# ftcontrol.net
KiCad netlist of a schematic drawn in EAGLE
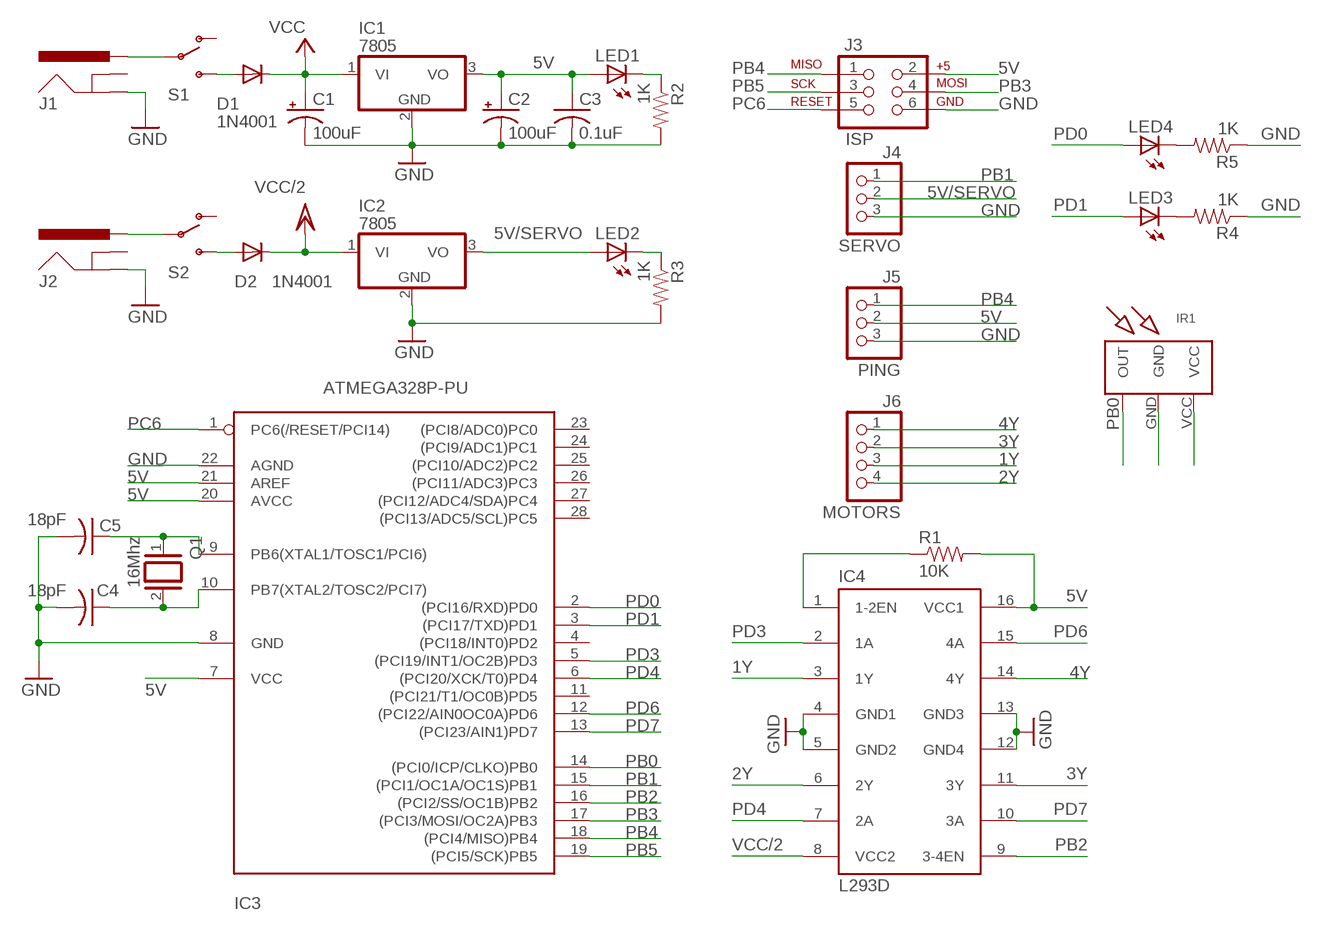
[diagram p0: schematic, sheet 1]

(export (version "E")
  (design (tool "Eeschema 10.0.6"))
  (components
    (comp (ref "C1")
      (value "100uF")
      (footprint "eagle-import:CPOL-RADIAL-100UF-25V")
      (libsource (lib "eagle-import") (part "CAP_POLPTH1"))
    )
    (comp (ref "C2")
      (value "100uF")
      (footprint "eagle-import:CPOL-RADIAL-10UF-25V")
      (libsource (lib "eagle-import") (part "CAP_POLPTH2"))
    )
    (comp (ref "C3")
      (value "0.1uF")
      (footprint "eagle-import:C025-025X050")
      (libsource (lib "eagle-import") (part "C-US025-025X050"))
    )
    (comp (ref "C4")
      (value "18pF")
      (footprint "eagle-import:C025-025X050")
      (libsource (lib "eagle-import") (part "C-US025-025X050"))
    )
    (comp (ref "C5")
      (value "18pF")
      (footprint "eagle-import:C025-025X050")
      (libsource (lib "eagle-import") (part "C-US025-025X050"))
    )
    (comp (ref "D1")
      (value "1N4001")
      (footprint "eagle-import:DIODE-1N4001")
      (libsource (lib "eagle-import") (part "DIODEPTH"))
    )
    (comp (ref "D2")
      (value "1N4001")
      (footprint "eagle-import:DIODE-1N4001")
      (libsource (lib "eagle-import") (part "DIODEPTH"))
    )
    (comp (ref "IC1")
      (value "7805")
      (footprint "eagle-import:TO220V")
      (libsource (lib "eagle-import") (part "78TV05"))
    )
    (comp (ref "IC2")
      (value "7805")
      (footprint "eagle-import:TO220V")
      (libsource (lib "eagle-import") (part "78TV05"))
    )
    (comp (ref "IC3")
      (value "ATMEGA328P-PU")
      (footprint "eagle-import:DIL28-3")
      (libsource (lib "eagle-import") (part "ATMEGA168P-20"))
    )
    (comp (ref "IC4")
      (value "L293D")
      (footprint "eagle-import:DIL16")
      (libsource (lib "eagle-import") (part "L293D"))
    )
    (comp (ref "IR1")
      (value "IR_TSOP4838")
      (footprint "eagle-import:TSOP_4838")
      (libsource (lib "eagle-import") (part "IR_TSOP4838"))
    )
    (comp (ref "J1")
      (value "POWER_JACKPTH")
      (footprint "eagle-import:POWER_JACK_PTH")
      (libsource (lib "eagle-import") (part "POWER_JACKPTH"))
    )
    (comp (ref "J2")
      (value "POWER_JACKPTH")
      (footprint "eagle-import:POWER_JACK_PTH")
      (libsource (lib "eagle-import") (part "POWER_JACKPTH"))
    )
    (comp (ref "J3")
      (value "ISP")
      (footprint "eagle-import:2X3")
      (libsource (lib "eagle-import") (part "AVR_SPI_PRG_6PTH"))
    )
    (comp (ref "J4")
      (value "SERVO")
      (footprint "eagle-import:1X03")
      (libsource (lib "eagle-import") (part "PINHD-1X3"))
    )
    (comp (ref "J5")
      (value "PING")
      (footprint "eagle-import:1X03")
      (libsource (lib "eagle-import") (part "PINHD-1X3"))
    )
    (comp (ref "J6")
      (value "MOTORS")
      (footprint "eagle-import:1X04")
      (libsource (lib "eagle-import") (part "PINHD-1X4"))
    )
    (comp (ref "LED1")
      (value "LED3MM")
      (footprint "eagle-import:LED3MM")
      (libsource (lib "eagle-import") (part "LED3MM"))
    )
    (comp (ref "LED2")
      (value "LED3MM")
      (footprint "eagle-import:LED3MM")
      (libsource (lib "eagle-import") (part "LED3MM"))
    )
    (comp (ref "LED3")
      (value "LED3MM")
      (footprint "eagle-import:LED3MM")
      (libsource (lib "eagle-import") (part "LED3MM"))
    )
    (comp (ref "LED4")
      (value "LED3MM")
      (footprint "eagle-import:LED3MM")
      (libsource (lib "eagle-import") (part "LED3MM"))
    )
    (comp (ref "Q1")
      (value "16Mhz")
      (footprint "eagle-import:QS")
      (libsource (lib "eagle-import") (part "XTAL/S"))
    )
    (comp (ref "R1")
      (value "10K")
      (footprint "eagle-import:AXIAL-0.4")
      (libsource (lib "eagle-import") (part "RESISTORPTH-1/4W"))
    )
    (comp (ref "R2")
      (value "1K")
      (footprint "eagle-import:AXIAL-0.4")
      (libsource (lib "eagle-import") (part "RESISTORPTH-1/4W"))
    )
    (comp (ref "R3")
      (value "1K")
      (footprint "eagle-import:AXIAL-0.4")
      (libsource (lib "eagle-import") (part "RESISTORPTH-1/4W"))
    )
    (comp (ref "R4")
      (value "1K")
      (footprint "eagle-import:AXIAL-0.4")
      (libsource (lib "eagle-import") (part "RESISTORPTH-1/4W"))
    )
    (comp (ref "R5")
      (value "1K")
      (footprint "eagle-import:AXIAL-0.4")
      (libsource (lib "eagle-import") (part "RESISTORPTH-1/4W"))
    )
    (comp (ref "S1")
      (value "SWITCH-SPDTPTH")
      (footprint "eagle-import:SWITCH-SPDT")
      (libsource (lib "eagle-import") (part "SWITCH-SPDTPTH"))
    )
    (comp (ref "S2")
      (value "SWITCH-SPDTPTH")
      (footprint "eagle-import:SWITCH-SPDT")
      (libsource (lib "eagle-import") (part "SWITCH-SPDTPTH"))
    )
  )
  (nets
    (net (code "1") (name "/1Y") (class "Default")
      (node (ref "IC4") (pin "3") (pinfunction "1Y_3") (pintype "output"))
      (node (ref "J6") (pin "3") (pinfunction "3_3") (pintype "passive"))
    )
    (net (code "2") (name "/2Y") (class "Default")
      (node (ref "IC4") (pin "6") (pinfunction "2Y_6") (pintype "output"))
      (node (ref "J6") (pin "4") (pinfunction "4_4") (pintype "passive"))
    )
    (net (code "3") (name "/3Y") (class "Default")
      (node (ref "IC4") (pin "11") (pinfunction "3Y_11") (pintype "output"))
      (node (ref "J6") (pin "2") (pinfunction "2_2") (pintype "passive"))
    )
    (net (code "4") (name "/4Y") (class "Default")
      (node (ref "IC4") (pin "14") (pinfunction "4Y_14") (pintype "output"))
      (node (ref "J6") (pin "1") (pinfunction "1_1") (pintype "passive"))
    )
    (net (code "5") (name "/5V") (class "Default")
      (node (ref "C2") (pin "1") (pinfunction "+_1") (pintype "passive"))
      (node (ref "C3") (pin "1") (pinfunction "1_1") (pintype "passive"))
      (node (ref "IC1") (pin "3") (pinfunction "VO_3") (pintype "passive"))
      (node (ref "IC3") (pin "20") (pinfunction "AVCC_20") (pintype "bidirectional"))
      (node (ref "IC3") (pin "21") (pinfunction "AREF_21") (pintype "bidirectional"))
      (node (ref "IC3") (pin "7") (pinfunction "VCC_7") (pintype "bidirectional"))
      (node (ref "IC4") (pin "16") (pinfunction "VCC1_16") (pintype "power_in"))
      (node (ref "IR1") (pin "VCC") (pinfunction "VCC_VCC") (pintype "bidirectional"))
      (node (ref "J3") (pin "2") (pinfunction "2_2") (pintype "passive"))
      (node (ref "J5") (pin "2") (pinfunction "2_2") (pintype "passive"))
      (node (ref "LED1") (pin "A") (pinfunction "A_A") (pintype "passive"))
      (node (ref "R1") (pin "P$2") (pinfunction "2_P$2") (pintype "passive"))
    )
    (net (code "6") (name "/5V{slash}SERVO") (class "Default")
      (node (ref "IC2") (pin "3") (pinfunction "VO_3") (pintype "passive"))
      (node (ref "J4") (pin "2") (pinfunction "2_2") (pintype "passive"))
      (node (ref "LED2") (pin "A") (pinfunction "A_A") (pintype "passive"))
    )
    (net (code "7") (name "/PB0") (class "Default")
      (node (ref "IC3") (pin "14") (pinfunction "(PCI0/ICP/CLKO)PB0_14") (pintype "bidirectional"))
      (node (ref "IR1") (pin "OUT") (pinfunction "OUT_OUT") (pintype "bidirectional"))
    )
    (net (code "8") (name "/PB1") (class "Default")
      (node (ref "IC3") (pin "15") (pinfunction "(PCI1/OC1A/OC1S)PB1_15") (pintype "bidirectional"))
      (node (ref "J4") (pin "1") (pinfunction "1_1") (pintype "passive"))
    )
    (net (code "9") (name "/PB2") (class "Default")
      (node (ref "IC3") (pin "16") (pinfunction "(PCI2/SS/OC1B)PB2_16") (pintype "bidirectional"))
      (node (ref "IC4") (pin "9") (pinfunction "3-4EN_9") (pintype "input"))
    )
    (net (code "10") (name "/PB3") (class "Default")
      (node (ref "IC3") (pin "17") (pinfunction "(PCI3/MOSI/OC2A)PB3_17") (pintype "bidirectional"))
      (node (ref "J3") (pin "4") (pinfunction "4_4") (pintype "passive"))
    )
    (net (code "11") (name "/PB4") (class "Default")
      (node (ref "IC3") (pin "18") (pinfunction "(PCI4/MISO)PB4_18") (pintype "bidirectional"))
      (node (ref "J3") (pin "1") (pinfunction "1_1") (pintype "passive"))
      (node (ref "J5") (pin "1") (pinfunction "1_1") (pintype "passive"))
    )
    (net (code "12") (name "/PB5") (class "Default")
      (node (ref "IC3") (pin "19") (pinfunction "(PCI5/SCK)PB5_19") (pintype "bidirectional"))
      (node (ref "J3") (pin "3") (pinfunction "3_3") (pintype "passive"))
    )
    (net (code "13") (name "/PC6") (class "Default")
      (node (ref "IC3") (pin "1") (pinfunction "PC6(/RESET/PCI14)_1") (pintype "bidirectional"))
      (node (ref "J3") (pin "5") (pinfunction "5_5") (pintype "passive"))
    )
    (net (code "14") (name "/PD0") (class "Default")
      (node (ref "IC3") (pin "2") (pinfunction "(PCI16/RXD)PD0_2") (pintype "bidirectional"))
      (node (ref "LED4") (pin "A") (pinfunction "A_A") (pintype "passive"))
    )
    (net (code "15") (name "/PD1") (class "Default")
      (node (ref "IC3") (pin "3") (pinfunction "(PCI17/TXD)PD1_3") (pintype "bidirectional"))
      (node (ref "LED3") (pin "A") (pinfunction "A_A") (pintype "passive"))
    )
    (net (code "16") (name "/PD3") (class "Default")
      (node (ref "IC3") (pin "5") (pinfunction "(PCI19/INT1/OC2B)PD3_5") (pintype "bidirectional"))
      (node (ref "IC4") (pin "2") (pinfunction "1A_2") (pintype "input"))
    )
    (net (code "17") (name "/PD4") (class "Default")
      (node (ref "IC3") (pin "6") (pinfunction "(PCI20/XCK/T0)PD4_6") (pintype "bidirectional"))
      (node (ref "IC4") (pin "7") (pinfunction "2A_7") (pintype "input"))
    )
    (net (code "18") (name "/PD6") (class "Default")
      (node (ref "IC3") (pin "12") (pinfunction "(PCI22/AIN0OC0A)PD6_12") (pintype "bidirectional"))
      (node (ref "IC4") (pin "15") (pinfunction "4A_15") (pintype "input"))
    )
    (net (code "19") (name "/PD7") (class "Default")
      (node (ref "IC3") (pin "13") (pinfunction "(PCI23/AIN1)PD7_13") (pintype "bidirectional"))
      (node (ref "IC4") (pin "10") (pinfunction "3A_10") (pintype "input"))
    )
    (net (code "20") (name "GND") (class "Default")
      (node (ref "C1") (pin "2") (pinfunction "-_2") (pintype "passive"))
      (node (ref "C2") (pin "2") (pinfunction "-_2") (pintype "passive"))
      (node (ref "C3") (pin "2") (pinfunction "2_2") (pintype "passive"))
      (node (ref "C4") (pin "2") (pinfunction "2_2") (pintype "passive"))
      (node (ref "C5") (pin "2") (pinfunction "2_2") (pintype "passive"))
      (node (ref "IC1") (pin "2") (pinfunction "GND_2") (pintype "passive"))
      (node (ref "IC2") (pin "2") (pinfunction "GND_2") (pintype "passive"))
      (node (ref "IC3") (pin "22") (pinfunction "AGND_22") (pintype "bidirectional"))
      (node (ref "IC3") (pin "8") (pinfunction "GND_8") (pintype "bidirectional"))
      (node (ref "IC4") (pin "12") (pinfunction "GND4_12") (pintype "power_in"))
      (node (ref "IC4") (pin "13") (pinfunction "GND3_13") (pintype "power_in"))
      (node (ref "IC4") (pin "4") (pinfunction "GND1_4") (pintype "power_in"))
      (node (ref "IC4") (pin "5") (pinfunction "GND2_5") (pintype "power_in"))
      (node (ref "IR1") (pin "GND") (pinfunction "GND_GND") (pintype "bidirectional"))
      (node (ref "J1") (pin "GND") (pinfunction "GND_GND") (pintype "bidirectional"))
      (node (ref "J2") (pin "GND") (pinfunction "GND_GND") (pintype "bidirectional"))
      (node (ref "J3") (pin "6") (pinfunction "6_6") (pintype "passive"))
      (node (ref "J4") (pin "3") (pinfunction "3_3") (pintype "passive"))
      (node (ref "J5") (pin "3") (pinfunction "3_3") (pintype "passive"))
      (node (ref "R2") (pin "P$2") (pinfunction "2_P$2") (pintype "passive"))
      (node (ref "R3") (pin "P$2") (pinfunction "2_P$2") (pintype "passive"))
      (node (ref "R4") (pin "P$1") (pinfunction "1_P$1") (pintype "passive"))
      (node (ref "R5") (pin "P$1") (pinfunction "1_P$1") (pintype "passive"))
    )
    (net (code "21") (name "Net-(IC3-PB6(XTAL1{slash}TOSC1{slash}PCI6))") (class "Default")
      (node (ref "C5") (pin "1") (pinfunction "1_1") (pintype "passive"))
      (node (ref "IC3") (pin "9") (pinfunction "PB6(XTAL1/TOSC1/PCI6)_9") (pintype "bidirectional"))
      (node (ref "Q1") (pin "1") (pinfunction "1_1") (pintype "passive"))
    )
    (net (code "22") (name "Net-(IC3-PB7(XTAL2{slash}TOSC2{slash}PCI7))") (class "Default")
      (node (ref "C4") (pin "1") (pinfunction "1_1") (pintype "passive"))
      (node (ref "IC3") (pin "10") (pinfunction "PB7(XTAL2/TOSC2/PCI7)_10") (pintype "bidirectional"))
      (node (ref "Q1") (pin "2") (pinfunction "2_2") (pintype "passive"))
    )
    (net (code "23") (name "Net-(IC4-1-2EN)") (class "Default")
      (node (ref "IC4") (pin "1") (pinfunction "1-2EN_1") (pintype "input"))
      (node (ref "R1") (pin "P$1") (pinfunction "1_P$1") (pintype "passive"))
    )
    (net (code "24") (name "Net-(LED1-C)") (class "Default")
      (node (ref "LED1") (pin "K") (pinfunction "C_K") (pintype "passive"))
      (node (ref "R2") (pin "P$1") (pinfunction "1_P$1") (pintype "passive"))
    )
    (net (code "25") (name "Net-(LED2-C)") (class "Default")
      (node (ref "LED2") (pin "K") (pinfunction "C_K") (pintype "passive"))
      (node (ref "R3") (pin "P$1") (pinfunction "1_P$1") (pintype "passive"))
    )
    (net (code "26") (name "Net-(LED3-C)") (class "Default")
      (node (ref "LED3") (pin "K") (pinfunction "C_K") (pintype "passive"))
      (node (ref "R4") (pin "P$2") (pinfunction "2_P$2") (pintype "passive"))
    )
    (net (code "27") (name "Net-(LED4-C)") (class "Default")
      (node (ref "LED4") (pin "K") (pinfunction "C_K") (pintype "passive"))
      (node (ref "R5") (pin "P$2") (pinfunction "2_P$2") (pintype "passive"))
    )
    (net (code "28") (name "Net-(S1-P)") (class "Default")
      (node (ref "J1") (pin "PWR") (pinfunction "PWR_PWR") (pintype "bidirectional"))
      (node (ref "S1") (pin "2") (pinfunction "P_2") (pintype "passive"))
    )
    (net (code "29") (name "Net-(S1-S)") (class "Default")
      (node (ref "D1") (pin "A") (pinfunction "A_A") (pintype "passive"))
      (node (ref "S1") (pin "3") (pinfunction "S_3") (pintype "passive"))
    )
    (net (code "30") (name "Net-(S2-P)") (class "Default")
      (node (ref "J2") (pin "PWR") (pinfunction "PWR_PWR") (pintype "bidirectional"))
      (node (ref "S2") (pin "2") (pinfunction "P_2") (pintype "passive"))
    )
    (net (code "31") (name "Net-(S2-S)") (class "Default")
      (node (ref "D2") (pin "A") (pinfunction "A_A") (pintype "passive"))
      (node (ref "S2") (pin "3") (pinfunction "S_3") (pintype "passive"))
    )
    (net (code "32") (name "VCC") (class "Default")
      (node (ref "C1") (pin "1") (pinfunction "+_1") (pintype "passive"))
      (node (ref "D1") (pin "C") (pinfunction "C_C") (pintype "passive"))
      (node (ref "IC1") (pin "1") (pinfunction "VI_1") (pintype "input"))
    )
    (net (code "33") (name "VCC{slash}2") (class "Default")
      (node (ref "D2") (pin "C") (pinfunction "C_C") (pintype "passive"))
      (node (ref "IC2") (pin "1") (pinfunction "VI_1") (pintype "input"))
      (node (ref "IC4") (pin "8") (pinfunction "VCC2_8") (pintype "power_in"))
    )
    (net (code "34") (name "unconnected-(IC3-(PCI8{slash}ADC0)PC0-Pad23)") (class "Default")
      (node (ref "IC3") (pin "23") (pinfunction "(PCI8/ADC0)PC0_23") (pintype "bidirectional"))
    )
    (net (code "35") (name "unconnected-(IC3-(PCI9{slash}ADC1)PC1-Pad24)") (class "Default")
      (node (ref "IC3") (pin "24") (pinfunction "(PCI9/ADC1)PC1_24") (pintype "bidirectional"))
    )
    (net (code "36") (name "unconnected-(IC3-(PCI10{slash}ADC2)PC2-Pad25)") (class "Default")
      (node (ref "IC3") (pin "25") (pinfunction "(PCI10/ADC2)PC2_25") (pintype "bidirectional"))
    )
    (net (code "37") (name "unconnected-(IC3-(PCI11{slash}ADC3)PC3-Pad26)") (class "Default")
      (node (ref "IC3") (pin "26") (pinfunction "(PCI11/ADC3)PC3_26") (pintype "bidirectional"))
    )
    (net (code "38") (name "unconnected-(IC3-(PCI12{slash}ADC4{slash}SDA)PC4-Pad27)") (class "Default")
      (node (ref "IC3") (pin "27") (pinfunction "(PCI12/ADC4/SDA)PC4_27") (pintype "bidirectional"))
    )
    (net (code "39") (name "unconnected-(IC3-(PCI13{slash}ADC5{slash}SCL)PC5-Pad28)") (class "Default")
      (node (ref "IC3") (pin "28") (pinfunction "(PCI13/ADC5/SCL)PC5_28") (pintype "bidirectional"))
    )
    (net (code "40") (name "unconnected-(IC3-(PCI18{slash}INT0)PD2-Pad4)") (class "Default")
      (node (ref "IC3") (pin "4") (pinfunction "(PCI18/INT0)PD2_4") (pintype "bidirectional"))
    )
    (net (code "41") (name "unconnected-(IC3-(PCI21{slash}T1{slash}OC0B)PD5-Pad11)") (class "Default")
      (node (ref "IC3") (pin "11") (pinfunction "(PCI21/T1/OC0B)PD5_11") (pintype "bidirectional"))
    )
    (net (code "42") (name "unconnected-(J1-PadGNDBREAK)") (class "Default")
      (node (ref "J1") (pin "GNDBREAK") (pinfunction "GNDBREAK_GNDBREAK") (pintype "bidirectional"))
    )
    (net (code "43") (name "unconnected-(J2-PadGNDBREAK)") (class "Default")
      (node (ref "J2") (pin "GNDBREAK") (pinfunction "GNDBREAK_GNDBREAK") (pintype "bidirectional"))
    )
    (net (code "44") (name "unconnected-(S1-O-Pad1)") (class "Default")
      (node (ref "S1") (pin "1") (pinfunction "O_1") (pintype "passive"))
    )
    (net (code "45") (name "unconnected-(S2-O-Pad1)") (class "Default")
      (node (ref "S2") (pin "1") (pinfunction "O_1") (pintype "passive"))
    )
  )
)
